# Functional_Module_main.net
KiCad netlist of a schematic drawn in Altium Designer
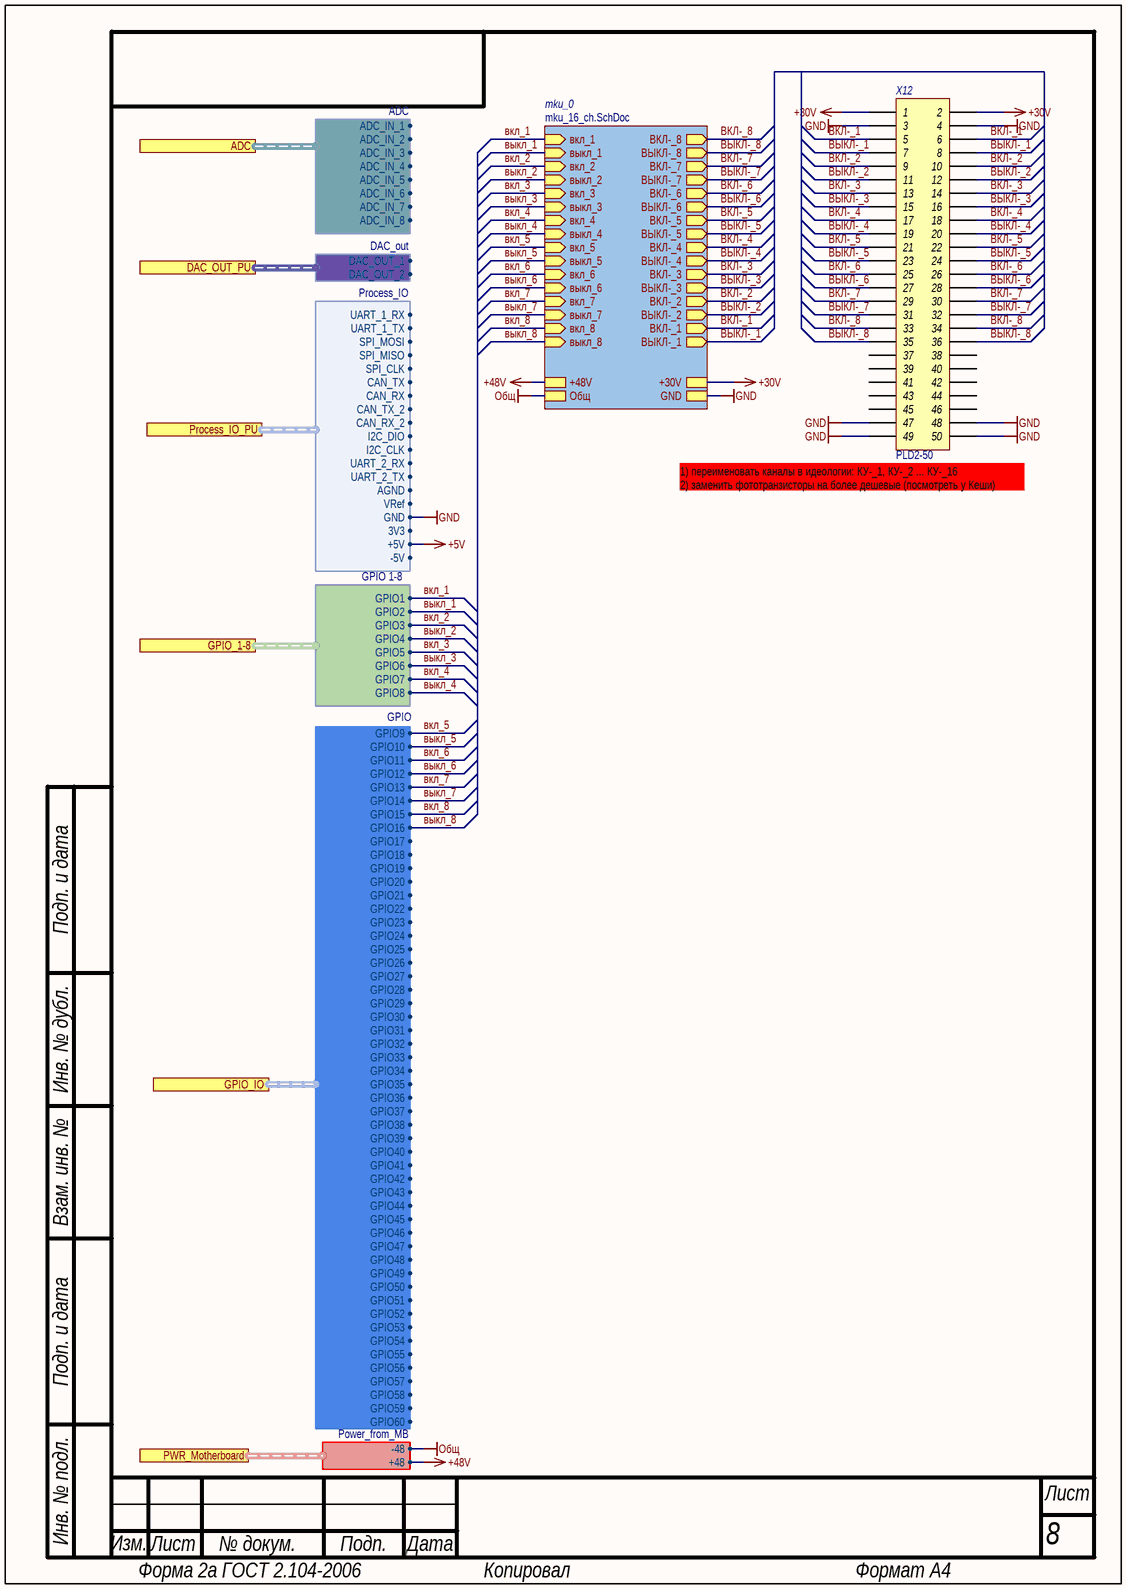
[diagram p0: Functional_Module_main.SchDoc]

(export (version "E")
  (design (tool "Eeschema 10.0.6"))
  (components
    (comp (ref "X12")
      (value "Header 2X25")
      (footprint "PLD2-50")
      (description "Header, 50-Pin, Dual row")
      (fields (field (name "НАИМЕНОВАНИЕ") "PLD2-50"))
      (libsource (lib "Connector") (part "PLD2-50"))
    )
  )
  (nets
    (net (code "8") (name "+30V") (class "Default")
      (node (ref "X12") (pin "1") (pinfunction "1_1") (pintype "passive"))
      (node (ref "X12") (pin "2") (pinfunction "2_2") (pintype "passive"))
    )
    (net (code "16") (name "/ВКЛ-_1") (class "Default")
      (node (ref "X12") (pin "5") (pinfunction "5_5") (pintype "passive"))
      (node (ref "X12") (pin "6") (pinfunction "6_6") (pintype "passive"))
    )
    (net (code "17") (name "/ВКЛ-_2") (class "Default")
      (node (ref "X12") (pin "10") (pinfunction "10_10") (pintype "passive"))
      (node (ref "X12") (pin "9") (pinfunction "9_9") (pintype "passive"))
    )
    (net (code "18") (name "/ВКЛ-_3") (class "Default")
      (node (ref "X12") (pin "13") (pinfunction "13_13") (pintype "passive"))
      (node (ref "X12") (pin "14") (pinfunction "14_14") (pintype "passive"))
    )
    (net (code "19") (name "/ВКЛ-_4") (class "Default")
      (node (ref "X12") (pin "17") (pinfunction "17_17") (pintype "passive"))
      (node (ref "X12") (pin "18") (pinfunction "18_18") (pintype "passive"))
    )
    (net (code "20") (name "/ВКЛ-_5") (class "Default")
      (node (ref "X12") (pin "21") (pinfunction "21_21") (pintype "passive"))
      (node (ref "X12") (pin "22") (pinfunction "22_22") (pintype "passive"))
    )
    (net (code "21") (name "/ВКЛ-_6") (class "Default")
      (node (ref "X12") (pin "25") (pinfunction "25_25") (pintype "passive"))
      (node (ref "X12") (pin "26") (pinfunction "26_26") (pintype "passive"))
    )
    (net (code "22") (name "/ВКЛ-_7") (class "Default")
      (node (ref "X12") (pin "29") (pinfunction "29_29") (pintype "passive"))
      (node (ref "X12") (pin "30") (pinfunction "30_30") (pintype "passive"))
    )
    (net (code "23") (name "/ВКЛ-_8") (class "Default")
      (node (ref "X12") (pin "33") (pinfunction "33_33") (pintype "passive"))
      (node (ref "X12") (pin "34") (pinfunction "34_34") (pintype "passive"))
    )
    (net (code "24") (name "/ВЫКЛ-_1") (class "Default")
      (node (ref "X12") (pin "7") (pinfunction "7_7") (pintype "passive"))
      (node (ref "X12") (pin "8") (pinfunction "8_8") (pintype "passive"))
    )
    (net (code "25") (name "/ВЫКЛ-_2") (class "Default")
      (node (ref "X12") (pin "11") (pinfunction "11_11") (pintype "passive"))
      (node (ref "X12") (pin "12") (pinfunction "12_12") (pintype "passive"))
    )
    (net (code "26") (name "/ВЫКЛ-_3") (class "Default")
      (node (ref "X12") (pin "15") (pinfunction "15_15") (pintype "passive"))
      (node (ref "X12") (pin "16") (pinfunction "16_16") (pintype "passive"))
    )
    (net (code "27") (name "/ВЫКЛ-_4") (class "Default")
      (node (ref "X12") (pin "19") (pinfunction "19_19") (pintype "passive"))
      (node (ref "X12") (pin "20") (pinfunction "20_20") (pintype "passive"))
    )
    (net (code "28") (name "/ВЫКЛ-_5") (class "Default")
      (node (ref "X12") (pin "23") (pinfunction "23_23") (pintype "passive"))
      (node (ref "X12") (pin "24") (pinfunction "24_24") (pintype "passive"))
    )
    (net (code "29") (name "/ВЫКЛ-_6") (class "Default")
      (node (ref "X12") (pin "27") (pinfunction "27_27") (pintype "passive"))
      (node (ref "X12") (pin "28") (pinfunction "28_28") (pintype "passive"))
    )
    (net (code "30") (name "/ВЫКЛ-_7") (class "Default")
      (node (ref "X12") (pin "31") (pinfunction "31_31") (pintype "passive"))
      (node (ref "X12") (pin "32") (pinfunction "32_32") (pintype "passive"))
    )
    (net (code "31") (name "/ВЫКЛ-_8") (class "Default")
      (node (ref "X12") (pin "35") (pinfunction "35_35") (pintype "passive"))
      (node (ref "X12") (pin "36") (pinfunction "36_36") (pintype "passive"))
    )
    (net (code "48") (name "GND") (class "Default")
      (node (ref "X12") (pin "3") (pinfunction "3_3") (pintype "passive"))
      (node (ref "X12") (pin "4") (pinfunction "4_4") (pintype "passive"))
      (node (ref "X12") (pin "47") (pinfunction "47_47") (pintype "passive"))
      (node (ref "X12") (pin "48") (pinfunction "48_48") (pintype "passive"))
      (node (ref "X12") (pin "49") (pinfunction "49_49") (pintype "passive"))
      (node (ref "X12") (pin "50") (pinfunction "50_50") (pintype "passive"))
    )
    (net (code "49") (name "unconnected-(X12-Pad37)") (class "Default")
      (node (ref "X12") (pin "37") (pinfunction "37_37") (pintype "passive"))
    )
    (net (code "50") (name "unconnected-(X12-Pad38)") (class "Default")
      (node (ref "X12") (pin "38") (pinfunction "38_38") (pintype "passive"))
    )
    (net (code "51") (name "unconnected-(X12-Pad39)") (class "Default")
      (node (ref "X12") (pin "39") (pinfunction "39_39") (pintype "passive"))
    )
    (net (code "52") (name "unconnected-(X12-Pad40)") (class "Default")
      (node (ref "X12") (pin "40") (pinfunction "40_40") (pintype "passive"))
    )
    (net (code "53") (name "unconnected-(X12-Pad41)") (class "Default")
      (node (ref "X12") (pin "41") (pinfunction "41_41") (pintype "passive"))
    )
    (net (code "54") (name "unconnected-(X12-Pad42)") (class "Default")
      (node (ref "X12") (pin "42") (pinfunction "42_42") (pintype "passive"))
    )
    (net (code "55") (name "unconnected-(X12-Pad43)") (class "Default")
      (node (ref "X12") (pin "43") (pinfunction "43_43") (pintype "passive"))
    )
    (net (code "56") (name "unconnected-(X12-Pad44)") (class "Default")
      (node (ref "X12") (pin "44") (pinfunction "44_44") (pintype "passive"))
    )
    (net (code "57") (name "unconnected-(X12-Pad45)") (class "Default")
      (node (ref "X12") (pin "45") (pinfunction "45_45") (pintype "passive"))
    )
    (net (code "58") (name "unconnected-(X12-Pad46)") (class "Default")
      (node (ref "X12") (pin "46") (pinfunction "46_46") (pintype "passive"))
    )
  )
)
